# micro_opto_v1_0.net
KiCad netlist of a schematic drawn in EAGLE
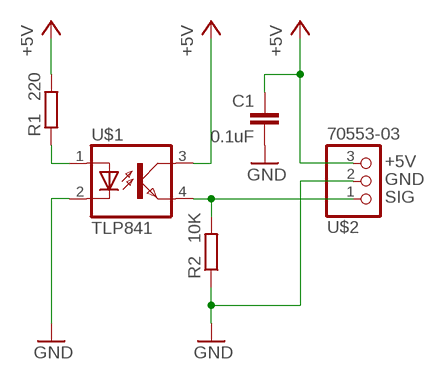
[diagram p0: schematic, sheet 1]

(export (version "E")
  (design (tool "Eeschema 10.0.6"))
  (components
    (comp (ref "C1")
      (value "0.1uF")
      (footprint "eagle-import:C0805")
      (libsource (lib "eagle-import") (part "C-EUC0805"))
    )
    (comp (ref "R1")
      (value "220")
      (footprint "eagle-import:R0805")
      (libsource (lib "eagle-import") (part "R-EU_R0805"))
    )
    (comp (ref "R2")
      (value "10K")
      (footprint "eagle-import:R0805")
      (libsource (lib "eagle-import") (part "R-EU_R0805"))
    )
    (comp (ref "U$1")
      (value "TLP841")
      (footprint "eagle-import:TLP841")
      (libsource (lib "eagle-import") (part "TLP841"))
    )
    (comp (ref "U$2")
      (value "70553-03")
      (footprint "eagle-import:70553-03")
      (libsource (lib "eagle-import") (part "70553-03"))
    )
  )
  (nets
    (net (code "1") (name "+5V") (class "Default")
      (node (ref "C1") (pin "1") (pinfunction "1_1") (pintype "passive"))
      (node (ref "R1") (pin "2") (pinfunction "2_2") (pintype "passive"))
      (node (ref "U$1") (pin "3") (pinfunction "COL_3") (pintype "passive"))
      (node (ref "U$2") (pin "3") (pinfunction "3_3") (pintype "passive"))
    )
    (net (code "2") (name "GND") (class "Default")
      (node (ref "C1") (pin "2") (pinfunction "2_2") (pintype "passive"))
      (node (ref "R2") (pin "1") (pinfunction "1_1") (pintype "passive"))
      (node (ref "U$1") (pin "2") (pinfunction "C_2") (pintype "passive"))
      (node (ref "U$2") (pin "2") (pinfunction "2_2") (pintype "passive"))
    )
    (net (code "3") (name "Net-(U$1-A)") (class "Default")
      (node (ref "R1") (pin "1") (pinfunction "1_1") (pintype "passive"))
      (node (ref "U$1") (pin "1") (pinfunction "A_1") (pintype "passive"))
    )
    (net (code "4") (name "Net-(U$1-EMIT)") (class "Default")
      (node (ref "R2") (pin "2") (pinfunction "2_2") (pintype "passive"))
      (node (ref "U$1") (pin "4") (pinfunction "EMIT_4") (pintype "passive"))
      (node (ref "U$2") (pin "1") (pinfunction "1_1") (pintype "passive"))
    )
  )
)
